# ADF4351_atmega8.net
KiCad netlist of a schematic drawn in EAGLE
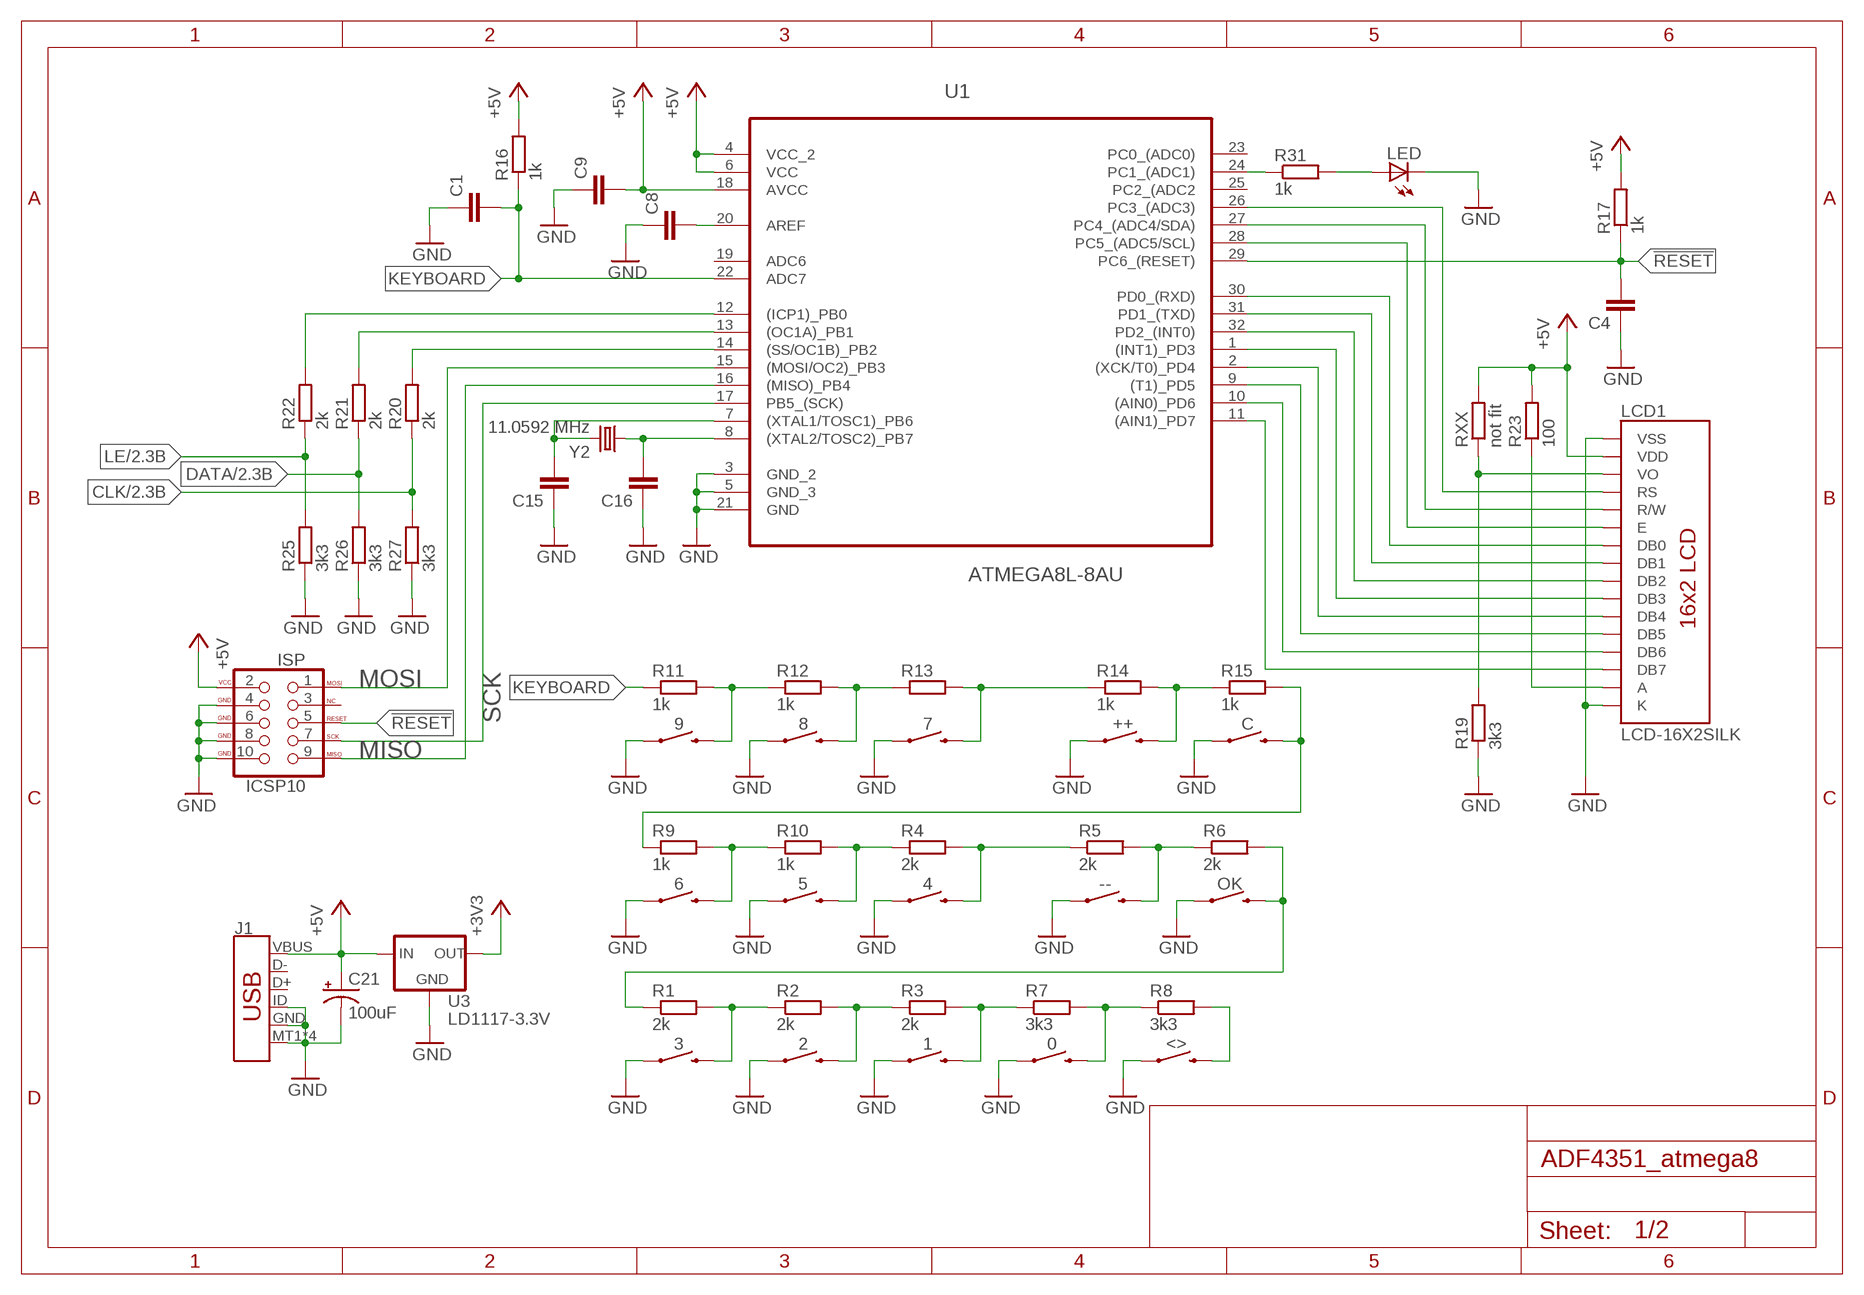
[diagram p0: schematic, sheet 1]
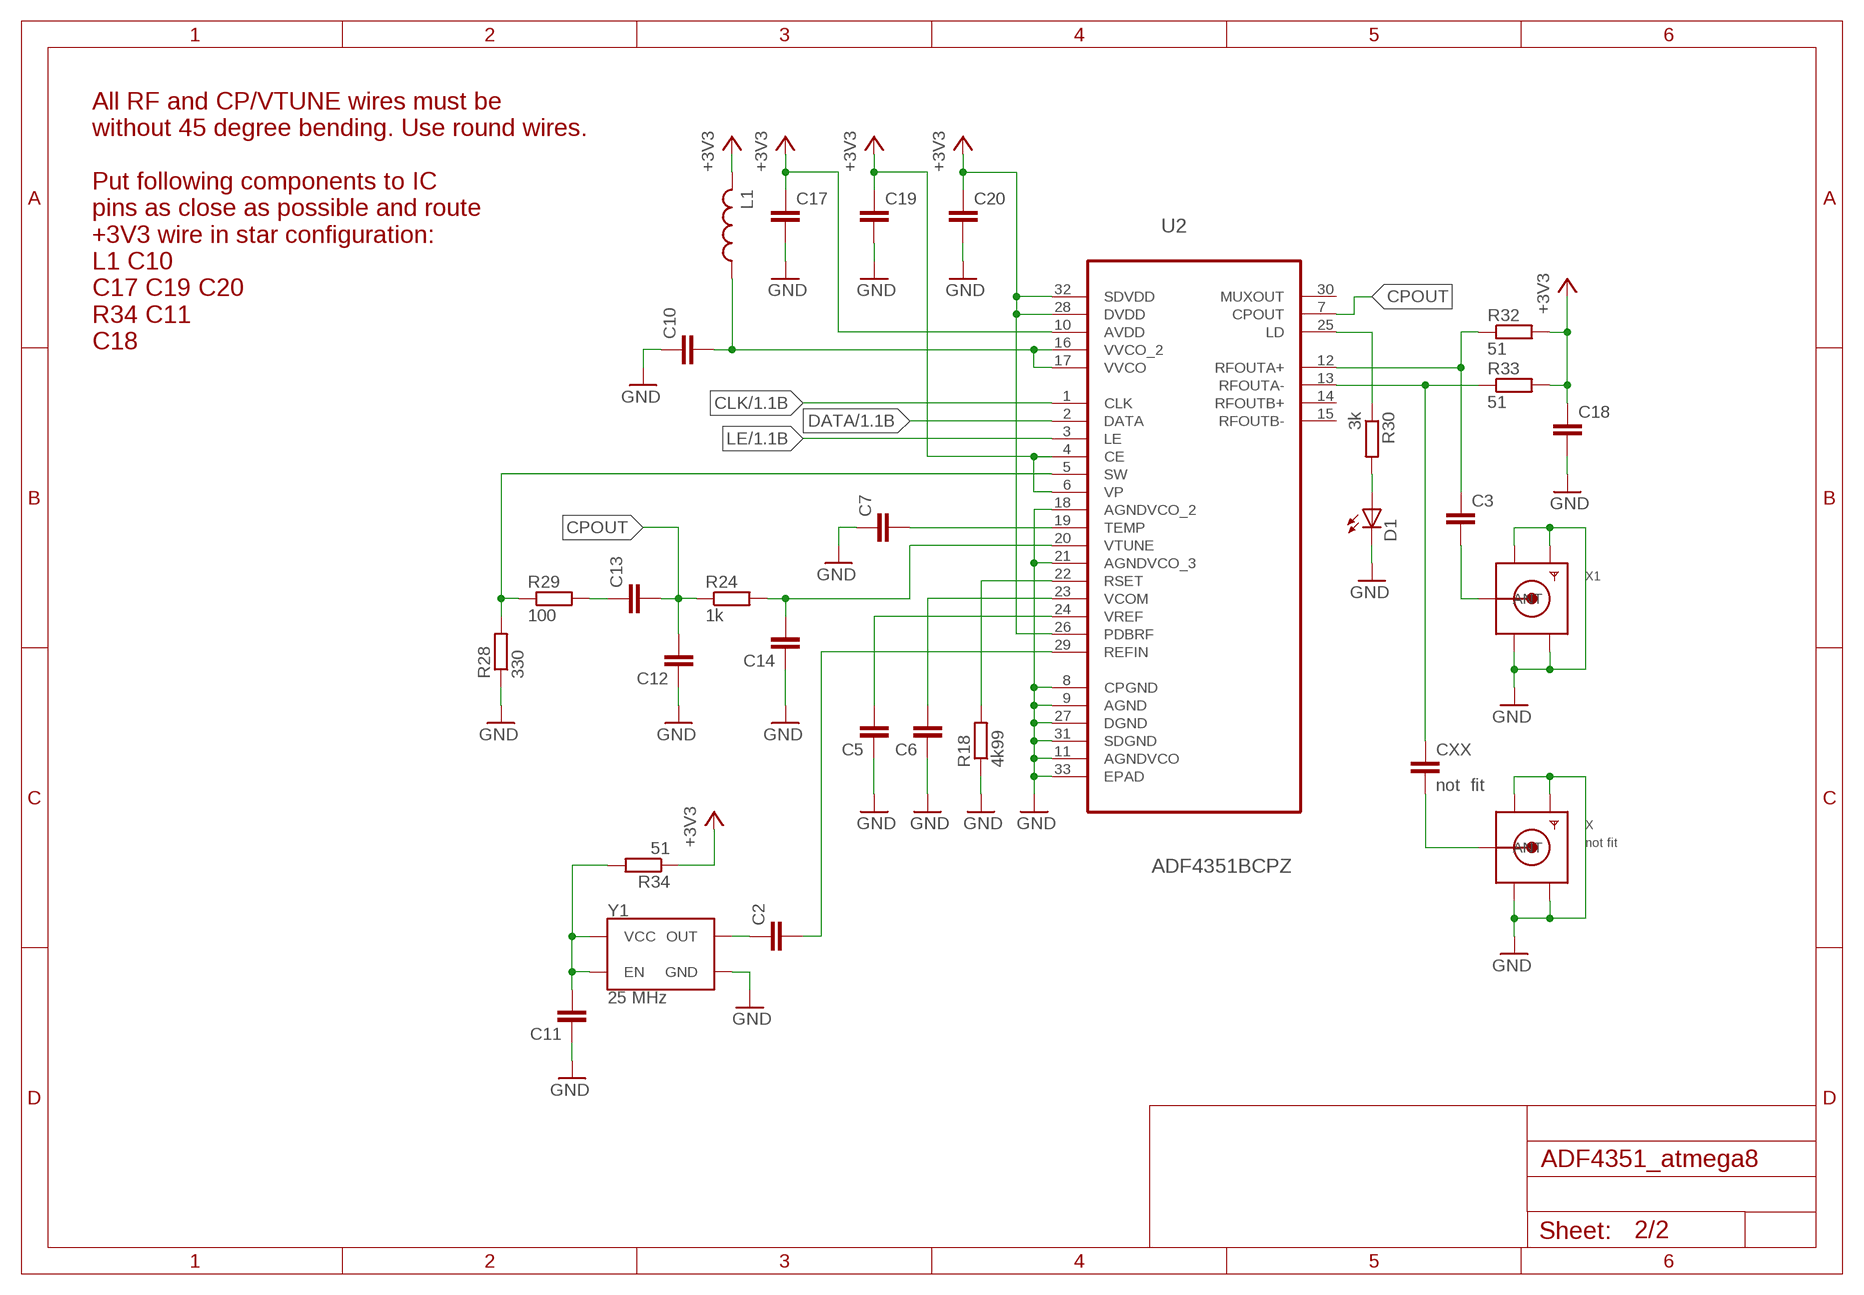
[diagram p1: schematic, sheet 2]

(export (version "E")
  (design (tool "Eeschema 10.0.6"))
  (components
    (comp (ref "C2")
      (value "C-EUC0805")
      (footprint "eagle-import:C0805")
      (libsource (lib "eagle-import") (part "C-EUC0805"))
    )
    (comp (ref "C3")
      (value "C-EUC0805")
      (footprint "eagle-import:C0805")
      (libsource (lib "eagle-import") (part "C-EUC0805"))
    )
    (comp (ref "C5")
      (value "C-EUC0805")
      (footprint "eagle-import:C0805")
      (libsource (lib "eagle-import") (part "C-EUC0805"))
    )
    (comp (ref "C6")
      (value "C-EUC0805")
      (footprint "eagle-import:C0805")
      (libsource (lib "eagle-import") (part "C-EUC0805"))
    )
    (comp (ref "C7")
      (value "C-EUC0805")
      (footprint "eagle-import:C0805")
      (libsource (lib "eagle-import") (part "C-EUC0805"))
    )
    (comp (ref "C10")
      (value "C-EUC0805")
      (footprint "eagle-import:C0805")
      (libsource (lib "eagle-import") (part "C-EUC0805"))
    )
    (comp (ref "C11")
      (value "C-EUC0805")
      (footprint "eagle-import:C0805")
      (libsource (lib "eagle-import") (part "C-EUC0805"))
    )
    (comp (ref "C12")
      (value "C-EUC0805")
      (footprint "eagle-import:C0805")
      (libsource (lib "eagle-import") (part "C-EUC0805"))
    )
    (comp (ref "C13")
      (value "C-EUC0805")
      (footprint "eagle-import:C0805")
      (libsource (lib "eagle-import") (part "C-EUC0805"))
    )
    (comp (ref "C14")
      (value "C-EUC0805")
      (footprint "eagle-import:C0805")
      (libsource (lib "eagle-import") (part "C-EUC0805"))
    )
    (comp (ref "C17")
      (value "C-EUC0805")
      (footprint "eagle-import:C0805")
      (libsource (lib "eagle-import") (part "C-EUC0805"))
    )
    (comp (ref "C18")
      (value "C-EUC0805")
      (footprint "eagle-import:C0805")
      (libsource (lib "eagle-import") (part "C-EUC0805"))
    )
    (comp (ref "C19")
      (value "C-EUC0805")
      (footprint "eagle-import:C0805")
      (libsource (lib "eagle-import") (part "C-EUC0805"))
    )
    (comp (ref "C20")
      (value "C-EUC0805")
      (footprint "eagle-import:C0805")
      (libsource (lib "eagle-import") (part "C-EUC0805"))
    )
    (comp (ref "CXX")
      (value "not fit")
      (footprint "eagle-import:C0805")
      (libsource (lib "eagle-import") (part "C-EUC0805"))
    )
    (comp (ref "D1")
      (value "LEDSML0805")
      (footprint "eagle-import:SML0805")
      (libsource (lib "eagle-import") (part "LEDSML0805"))
    )
    (comp (ref "L1")
      (value "L-USL2012C")
      (footprint "eagle-import:L2012C")
      (libsource (lib "eagle-import") (part "L-USL2012C"))
    )
    (comp (ref "R18")
      (value "4k99")
      (footprint "eagle-import:R0805")
      (libsource (lib "eagle-import") (part "R-EU_R0805"))
    )
    (comp (ref "R24")
      (value "1k")
      (footprint "eagle-import:R0805")
      (libsource (lib "eagle-import") (part "R-EU_R0805"))
    )
    (comp (ref "R28")
      (value "330")
      (footprint "eagle-import:R0805")
      (libsource (lib "eagle-import") (part "R-EU_R0805"))
    )
    (comp (ref "R29")
      (value "100")
      (footprint "eagle-import:R0805")
      (libsource (lib "eagle-import") (part "R-EU_R0805"))
    )
    (comp (ref "R30")
      (value "3k")
      (footprint "eagle-import:R0805")
      (libsource (lib "eagle-import") (part "R-EU_R0805"))
    )
    (comp (ref "R32")
      (value "51")
      (footprint "eagle-import:R0805")
      (libsource (lib "eagle-import") (part "R-EU_R0805"))
    )
    (comp (ref "R33")
      (value "51")
      (footprint "eagle-import:R0805")
      (libsource (lib "eagle-import") (part "R-EU_R0805"))
    )
    (comp (ref "R34")
      (value "51")
      (footprint "eagle-import:R0805")
      (libsource (lib "eagle-import") (part "R-EU_R0805"))
    )
    (comp (ref "U2")
      (value "ADF4351BCPZ")
      (footprint "eagle-import:QFN50P500X500X100-33N")
      (libsource (lib "eagle-import") (part "ADF4351BCPZ"))
    )
    (comp (ref "X")
      (value "not fit")
      (footprint "eagle-import:SMA_EDGELAUNCH")
      (libsource (lib "eagle-import") (part "SMACONNECTOR_EDGE"))
    )
    (comp (ref "X1")
      (value "SMACONNECTOR_EDGE")
      (footprint "eagle-import:SMA_EDGELAUNCH")
      (libsource (lib "eagle-import") (part "SMACONNECTOR_EDGE"))
    )
    (comp (ref "Y1")
      (value "25 MHz")
      (footprint "eagle-import:OSCILLATOR-SMD-7X5-4PAD")
      (libsource (lib "eagle-import") (part "OSCILLATORSMD-7X5-4PAD"))
    )
    (comp (ref "++")
      (value "MOMENTARY-SWITCH-SPST-SMD-6.2MM-TALL")
      (footprint "eagle-import:TACTILE_SWITCH_SMD_6.2MM_TALL")
      (libsource (lib "eagle-import") (part "MOMENTARY-SWITCH-SPST-SMD-6.2MM-TALL"))
    )
    (comp (ref "--")
      (value "MOMENTARY-SWITCH-SPST-SMD-6.2MM-TALL")
      (footprint "eagle-import:TACTILE_SWITCH_SMD_6.2MM_TALL")
      (libsource (lib "eagle-import") (part "MOMENTARY-SWITCH-SPST-SMD-6.2MM-TALL"))
    )
    (comp (ref "0")
      (value "MOMENTARY-SWITCH-SPST-SMD-6.2MM-TALL")
      (footprint "eagle-import:TACTILE_SWITCH_SMD_6.2MM_TALL")
      (libsource (lib "eagle-import") (part "MOMENTARY-SWITCH-SPST-SMD-6.2MM-TALL"))
    )
    (comp (ref "1")
      (value "MOMENTARY-SWITCH-SPST-SMD-6.2MM-TALL")
      (footprint "eagle-import:TACTILE_SWITCH_SMD_6.2MM_TALL")
      (libsource (lib "eagle-import") (part "MOMENTARY-SWITCH-SPST-SMD-6.2MM-TALL"))
    )
    (comp (ref "2")
      (value "MOMENTARY-SWITCH-SPST-SMD-6.2MM-TALL")
      (footprint "eagle-import:TACTILE_SWITCH_SMD_6.2MM_TALL")
      (libsource (lib "eagle-import") (part "MOMENTARY-SWITCH-SPST-SMD-6.2MM-TALL"))
    )
    (comp (ref "3")
      (value "MOMENTARY-SWITCH-SPST-SMD-6.2MM-TALL")
      (footprint "eagle-import:TACTILE_SWITCH_SMD_6.2MM_TALL")
      (libsource (lib "eagle-import") (part "MOMENTARY-SWITCH-SPST-SMD-6.2MM-TALL"))
    )
    (comp (ref "4")
      (value "MOMENTARY-SWITCH-SPST-SMD-6.2MM-TALL")
      (footprint "eagle-import:TACTILE_SWITCH_SMD_6.2MM_TALL")
      (libsource (lib "eagle-import") (part "MOMENTARY-SWITCH-SPST-SMD-6.2MM-TALL"))
    )
    (comp (ref "5")
      (value "MOMENTARY-SWITCH-SPST-SMD-6.2MM-TALL")
      (footprint "eagle-import:TACTILE_SWITCH_SMD_6.2MM_TALL")
      (libsource (lib "eagle-import") (part "MOMENTARY-SWITCH-SPST-SMD-6.2MM-TALL"))
    )
    (comp (ref "6")
      (value "MOMENTARY-SWITCH-SPST-SMD-6.2MM-TALL")
      (footprint "eagle-import:TACTILE_SWITCH_SMD_6.2MM_TALL")
      (libsource (lib "eagle-import") (part "MOMENTARY-SWITCH-SPST-SMD-6.2MM-TALL"))
    )
    (comp (ref "7")
      (value "MOMENTARY-SWITCH-SPST-SMD-6.2MM-TALL")
      (footprint "eagle-import:TACTILE_SWITCH_SMD_6.2MM_TALL")
      (libsource (lib "eagle-import") (part "MOMENTARY-SWITCH-SPST-SMD-6.2MM-TALL"))
    )
    (comp (ref "8")
      (value "MOMENTARY-SWITCH-SPST-SMD-6.2MM-TALL")
      (footprint "eagle-import:TACTILE_SWITCH_SMD_6.2MM_TALL")
      (libsource (lib "eagle-import") (part "MOMENTARY-SWITCH-SPST-SMD-6.2MM-TALL"))
    )
    (comp (ref "9")
      (value "MOMENTARY-SWITCH-SPST-SMD-6.2MM-TALL")
      (footprint "eagle-import:TACTILE_SWITCH_SMD_6.2MM_TALL")
      (libsource (lib "eagle-import") (part "MOMENTARY-SWITCH-SPST-SMD-6.2MM-TALL"))
    )
    (comp (ref "<>")
      (value "MOMENTARY-SWITCH-SPST-SMD-6.2MM-TALL")
      (footprint "eagle-import:TACTILE_SWITCH_SMD_6.2MM_TALL")
      (libsource (lib "eagle-import") (part "MOMENTARY-SWITCH-SPST-SMD-6.2MM-TALL"))
    )
    (comp (ref "C")
      (value "MOMENTARY-SWITCH-SPST-SMD-6.2MM-TALL")
      (footprint "eagle-import:TACTILE_SWITCH_SMD_6.2MM_TALL")
      (libsource (lib "eagle-import") (part "MOMENTARY-SWITCH-SPST-SMD-6.2MM-TALL"))
    )
    (comp (ref "C1")
      (value "C-EUC0805")
      (footprint "eagle-import:C0805")
      (libsource (lib "eagle-import") (part "C-EUC0805"))
    )
    (comp (ref "C4")
      (value "C-EUC0805")
      (footprint "eagle-import:C0805")
      (libsource (lib "eagle-import") (part "C-EUC0805"))
    )
    (comp (ref "C8")
      (value "C-EUC0805")
      (footprint "eagle-import:C0805")
      (libsource (lib "eagle-import") (part "C-EUC0805"))
    )
    (comp (ref "C9")
      (value "C-EUC0805")
      (footprint "eagle-import:C0805")
      (libsource (lib "eagle-import") (part "C-EUC0805"))
    )
    (comp (ref "C15")
      (value "C-EUC0805")
      (footprint "eagle-import:C0805")
      (libsource (lib "eagle-import") (part "C-EUC0805"))
    )
    (comp (ref "C16")
      (value "C-EUC0805")
      (footprint "eagle-import:C0805")
      (libsource (lib "eagle-import") (part "C-EUC0805"))
    )
    (comp (ref "C21")
      (value "100uF")
      (footprint "eagle-import:E5-5")
      (libsource (lib "eagle-import") (part "CPOL-USE5-5"))
    )
    (comp (ref "ISP")
      (value "ICSP10")
      (footprint "eagle-import:2X5")
      (libsource (lib "eagle-import") (part "AVR_SPI_PROG_5X2PTH"))
    )
    (comp (ref "J1")
      (value "USB_MICRO-B_SMT")
      (footprint "eagle-import:USB-MICROB")
      (libsource (lib "eagle-import") (part "USB_MICRO-B_SMT"))
    )
    (comp (ref "LCD1")
      (value "LCD-16X2SILK")
      (footprint "eagle-import:LCD-16X2")
      (libsource (lib "eagle-import") (part "LCD-16X2SILK"))
    )
    (comp (ref "LED")
      (value "LEDSML0805")
      (footprint "eagle-import:SML0805")
      (libsource (lib "eagle-import") (part "LEDSML0805"))
    )
    (comp (ref "OK")
      (value "MOMENTARY-SWITCH-SPST-SMD-6.2MM-TALL")
      (footprint "eagle-import:TACTILE_SWITCH_SMD_6.2MM_TALL")
      (libsource (lib "eagle-import") (part "MOMENTARY-SWITCH-SPST-SMD-6.2MM-TALL"))
    )
    (comp (ref "R1")
      (value "2k")
      (footprint "eagle-import:R0805")
      (libsource (lib "eagle-import") (part "R-EU_R0805"))
    )
    (comp (ref "R2")
      (value "2k")
      (footprint "eagle-import:R0805")
      (libsource (lib "eagle-import") (part "R-EU_R0805"))
    )
    (comp (ref "R3")
      (value "2k")
      (footprint "eagle-import:R0805")
      (libsource (lib "eagle-import") (part "R-EU_R0805"))
    )
    (comp (ref "R4")
      (value "2k")
      (footprint "eagle-import:R0805")
      (libsource (lib "eagle-import") (part "R-EU_R0805"))
    )
    (comp (ref "R5")
      (value "2k")
      (footprint "eagle-import:R0805")
      (libsource (lib "eagle-import") (part "R-EU_R0805"))
    )
    (comp (ref "R6")
      (value "2k")
      (footprint "eagle-import:R0805")
      (libsource (lib "eagle-import") (part "R-EU_R0805"))
    )
    (comp (ref "R7")
      (value "3k3")
      (footprint "eagle-import:R0805")
      (libsource (lib "eagle-import") (part "R-EU_R0805"))
    )
    (comp (ref "R8")
      (value "3k3")
      (footprint "eagle-import:R0805")
      (libsource (lib "eagle-import") (part "R-EU_R0805"))
    )
    (comp (ref "R9")
      (value "1k")
      (footprint "eagle-import:R0805")
      (libsource (lib "eagle-import") (part "R-EU_R0805"))
    )
    (comp (ref "R10")
      (value "1k")
      (footprint "eagle-import:R0805")
      (libsource (lib "eagle-import") (part "R-EU_R0805"))
    )
    (comp (ref "R11")
      (value "1k")
      (footprint "eagle-import:R0805")
      (libsource (lib "eagle-import") (part "R-EU_R0805"))
    )
    (comp (ref "R12")
      (value "1k")
      (footprint "eagle-import:R0805")
      (libsource (lib "eagle-import") (part "R-EU_R0805"))
    )
    (comp (ref "R13")
      (value "R-EU_R0805")
      (footprint "eagle-import:R0805")
      (libsource (lib "eagle-import") (part "R-EU_R0805"))
    )
    (comp (ref "R14")
      (value "1k")
      (footprint "eagle-import:R0805")
      (libsource (lib "eagle-import") (part "R-EU_R0805"))
    )
    (comp (ref "R15")
      (value "1k")
      (footprint "eagle-import:R0805")
      (libsource (lib "eagle-import") (part "R-EU_R0805"))
    )
    (comp (ref "R16")
      (value "1k")
      (footprint "eagle-import:R0805")
      (libsource (lib "eagle-import") (part "R-EU_R0805"))
    )
    (comp (ref "R17")
      (value "1k")
      (footprint "eagle-import:R0805")
      (libsource (lib "eagle-import") (part "R-EU_R0805"))
    )
    (comp (ref "R19")
      (value "3k3")
      (footprint "eagle-import:R0805")
      (libsource (lib "eagle-import") (part "R-EU_R0805"))
    )
    (comp (ref "R20")
      (value "2k")
      (footprint "eagle-import:R0805")
      (libsource (lib "eagle-import") (part "R-EU_R0805"))
    )
    (comp (ref "R21")
      (value "2k")
      (footprint "eagle-import:R0805")
      (libsource (lib "eagle-import") (part "R-EU_R0805"))
    )
    (comp (ref "R22")
      (value "2k")
      (footprint "eagle-import:R0805")
      (libsource (lib "eagle-import") (part "R-EU_R0805"))
    )
    (comp (ref "R23")
      (value "100")
      (footprint "eagle-import:R0805")
      (libsource (lib "eagle-import") (part "R-EU_R0805"))
    )
    (comp (ref "R25")
      (value "3k3")
      (footprint "eagle-import:R0805")
      (libsource (lib "eagle-import") (part "R-EU_R0805"))
    )
    (comp (ref "R26")
      (value "3k3")
      (footprint "eagle-import:R0805")
      (libsource (lib "eagle-import") (part "R-EU_R0805"))
    )
    (comp (ref "R27")
      (value "3k3")
      (footprint "eagle-import:R0805")
      (libsource (lib "eagle-import") (part "R-EU_R0805"))
    )
    (comp (ref "R31")
      (value "1k")
      (footprint "eagle-import:R0805")
      (libsource (lib "eagle-import") (part "R-EU_R0805"))
    )
    (comp (ref "RXX")
      (value "not fit")
      (footprint "eagle-import:R0805")
      (libsource (lib "eagle-import") (part "R-EU_R0805"))
    )
    (comp (ref "U1")
      (value "ATMEGA8L-8AU")
      (footprint "eagle-import:QFP80P900X900X120-32N")
      (libsource (lib "eagle-import") (part "ATMEGA8L-8AU"))
    )
    (comp (ref "U3")
      (value "LD1117-3.3V")
      (footprint "eagle-import:SOT223")
      (libsource (lib "eagle-import") (part "V_REG_LD1117VXXLD1117-SMD"))
    )
    (comp (ref "Y2")
      (value "11.0592 MHz")
      (footprint "eagle-import:HC49_S")
      (libsource (lib "eagle-import") (part "CRYSTALHC49S"))
    )
  )
  (nets
    (net (code "1") (name "+3V3") (class "Default")
      (node (ref "C17") (pin "1") (pinfunction "1_1") (pintype "passive"))
      (node (ref "C18") (pin "1") (pinfunction "1_1") (pintype "passive"))
      (node (ref "C19") (pin "1") (pinfunction "1_1") (pintype "passive"))
      (node (ref "C20") (pin "1") (pinfunction "1_1") (pintype "passive"))
      (node (ref "L1") (pin "2") (pinfunction "2_2") (pintype "passive"))
      (node (ref "R32") (pin "2") (pinfunction "2_2") (pintype "passive"))
      (node (ref "R33") (pin "2") (pinfunction "2_2") (pintype "passive"))
      (node (ref "R34") (pin "1") (pinfunction "1_1") (pintype "passive"))
      (node (ref "U2") (pin "10") (pinfunction "AVDD_10") (pintype "power_in"))
      (node (ref "U2") (pin "26") (pinfunction "PDBRF_26") (pintype "passive"))
      (node (ref "U2") (pin "28") (pinfunction "DVDD_28") (pintype "power_in"))
      (node (ref "U2") (pin "32") (pinfunction "SDVDD_32") (pintype "passive"))
      (node (ref "U2") (pin "4") (pinfunction "CE_4") (pintype "input"))
      (node (ref "U2") (pin "6") (pinfunction "VP_6") (pintype "power_in"))
      (node (ref "U3") (pin "2") (pinfunction "OUT_2") (pintype "passive"))
    )
    (net (code "2") (name "+5V") (class "Default")
      (node (ref "C21") (pin "+") (pinfunction "+_+") (pintype "passive"))
      (node (ref "C9") (pin "2") (pinfunction "2_2") (pintype "passive"))
      (node (ref "ISP") (pin "2") (pinfunction "VCC_2") (pintype "power_in"))
      (node (ref "J1") (pin "VBUS") (pinfunction "VBUS_VBUS") (pintype "power_in"))
      (node (ref "LCD1") (pin "2") (pinfunction "VDD_2") (pintype "power_in"))
      (node (ref "R16") (pin "2") (pinfunction "2_2") (pintype "passive"))
      (node (ref "R17") (pin "2") (pinfunction "2_2") (pintype "passive"))
      (node (ref "R23") (pin "2") (pinfunction "2_2") (pintype "passive"))
      (node (ref "RXX") (pin "2") (pinfunction "2_2") (pintype "passive"))
      (node (ref "U1") (pin "18") (pinfunction "AVCC_18") (pintype "power_in"))
      (node (ref "U1") (pin "4") (pinfunction "VCC_2_4") (pintype "power_in"))
      (node (ref "U1") (pin "6") (pinfunction "VCC_6") (pintype "power_in"))
      (node (ref "U3") (pin "3") (pinfunction "IN_3") (pintype "input"))
    )
    (net (code "3") (name "CLK") (class "Default")
      (node (ref "R20") (pin "1") (pinfunction "1_1") (pintype "passive"))
      (node (ref "R27") (pin "2") (pinfunction "2_2") (pintype "passive"))
      (node (ref "U2") (pin "1") (pinfunction "CLK_1") (pintype "input"))
    )
    (net (code "4") (name "CPOUT") (class "Default")
      (node (ref "C12") (pin "2") (pinfunction "2_2") (pintype "passive"))
      (node (ref "C13") (pin "2") (pinfunction "2_2") (pintype "passive"))
      (node (ref "R24") (pin "1") (pinfunction "1_1") (pintype "passive"))
      (node (ref "U2") (pin "7") (pinfunction "CPOUT_7") (pintype "output"))
    )
    (net (code "5") (name "DATA") (class "Default")
      (node (ref "R21") (pin "1") (pinfunction "1_1") (pintype "passive"))
      (node (ref "R26") (pin "2") (pinfunction "2_2") (pintype "passive"))
      (node (ref "U2") (pin "2") (pinfunction "DATA_2") (pintype "input"))
    )
    (net (code "6") (name "GND") (class "Default")
      (node (ref "++") (pin "A2") (pinfunction "1_A2") (pintype "passive"))
      (node (ref "--") (pin "A2") (pinfunction "1_A2") (pintype "passive"))
      (node (ref "0") (pin "A2") (pinfunction "1_A2") (pintype "passive"))
      (node (ref "1") (pin "A2") (pinfunction "1_A2") (pintype "passive"))
      (node (ref "2") (pin "A2") (pinfunction "1_A2") (pintype "passive"))
      (node (ref "3") (pin "A2") (pinfunction "1_A2") (pintype "passive"))
      (node (ref "4") (pin "A2") (pinfunction "1_A2") (pintype "passive"))
      (node (ref "5") (pin "A2") (pinfunction "1_A2") (pintype "passive"))
      (node (ref "6") (pin "A2") (pinfunction "1_A2") (pintype "passive"))
      (node (ref "7") (pin "A2") (pinfunction "1_A2") (pintype "passive"))
      (node (ref "8") (pin "A2") (pinfunction "1_A2") (pintype "passive"))
      (node (ref "9") (pin "A2") (pinfunction "1_A2") (pintype "passive"))
      (node (ref "<>") (pin "A2") (pinfunction "1_A2") (pintype "passive"))
      (node (ref "C") (pin "A2") (pinfunction "1_A2") (pintype "passive"))
      (node (ref "C1") (pin "1") (pinfunction "1_1") (pintype "passive"))
      (node (ref "C10") (pin "1") (pinfunction "1_1") (pintype "passive"))
      (node (ref "C11") (pin "1") (pinfunction "1_1") (pintype "passive"))
      (node (ref "C12") (pin "1") (pinfunction "1_1") (pintype "passive"))
      (node (ref "C14") (pin "1") (pinfunction "1_1") (pintype "passive"))
      (node (ref "C15") (pin "1") (pinfunction "1_1") (pintype "passive"))
      (node (ref "C16") (pin "1") (pinfunction "1_1") (pintype "passive"))
      (node (ref "C17") (pin "2") (pinfunction "2_2") (pintype "passive"))
      (node (ref "C18") (pin "2") (pinfunction "2_2") (pintype "passive"))
      (node (ref "C19") (pin "2") (pinfunction "2_2") (pintype "passive"))
      (node (ref "C20") (pin "2") (pinfunction "2_2") (pintype "passive"))
      (node (ref "C21") (pin "-") (pinfunction "-_-") (pintype "passive"))
      (node (ref "C4") (pin "1") (pinfunction "1_1") (pintype "passive"))
      (node (ref "C5") (pin "1") (pinfunction "1_1") (pintype "passive"))
      (node (ref "C6") (pin "1") (pinfunction "1_1") (pintype "passive"))
      (node (ref "C7") (pin "1") (pinfunction "1_1") (pintype "passive"))
      (node (ref "C8") (pin "1") (pinfunction "1_1") (pintype "passive"))
      (node (ref "C9") (pin "1") (pinfunction "1_1") (pintype "passive"))
      (node (ref "D1") (pin "C") (pinfunction "C_C") (pintype "passive"))
      (node (ref "ISP") (pin "10") (pinfunction "GND_10") (pintype "power_in"))
      (node (ref "ISP") (pin "4") (pinfunction "GND_4") (pintype "power_in"))
      (node (ref "ISP") (pin "6") (pinfunction "GND_6") (pintype "power_in"))
      (node (ref "ISP") (pin "8") (pinfunction "GND_8") (pintype "power_in"))
      (node (ref "J1") (pin "GND") (pinfunction "GND_GND") (pintype "power_in"))
      (node (ref "J1") (pin "ID") (pinfunction "ID_ID") (pintype "bidirectional"))
      (node (ref "J1") (pin "MT1") (pinfunction "SHIELD_MT1") (pintype "bidirectional"))
      (node (ref "J1") (pin "MT2") (pinfunction "SHIELD_MT2") (pintype "bidirectional"))
      (node (ref "J1") (pin "P$1") (pinfunction "SHIELD_P$1") (pintype "bidirectional"))
      (node (ref "J1") (pin "P$2") (pinfunction "SHIELD_P$2") (pintype "bidirectional"))
      (node (ref "LCD1") (pin "1") (pinfunction "VSS_1") (pintype "power_in"))
      (node (ref "LCD1") (pin "16") (pinfunction "K_16") (pintype "power_in"))
      (node (ref "LED") (pin "C") (pinfunction "C_C") (pintype "passive"))
      (node (ref "OK") (pin "A2") (pinfunction "1_A2") (pintype "passive"))
      (node (ref "R18") (pin "1") (pinfunction "1_1") (pintype "passive"))
      (node (ref "R19") (pin "1") (pinfunction "1_1") (pintype "passive"))
      (node (ref "R25") (pin "1") (pinfunction "1_1") (pintype "passive"))
      (node (ref "R26") (pin "1") (pinfunction "1_1") (pintype "passive"))
      (node (ref "R27") (pin "1") (pinfunction "1_1") (pintype "passive"))
      (node (ref "R28") (pin "1") (pinfunction "1_1") (pintype "passive"))
      (node (ref "U1") (pin "21") (pinfunction "GND_21") (pintype "passive"))
      (node (ref "U1") (pin "3") (pinfunction "GND_2_3") (pintype "passive"))
      (node (ref "U1") (pin "5") (pinfunction "GND_3_5") (pintype "passive"))
      (node (ref "U2") (pin "11") (pinfunction "AGNDVCO_11") (pintype "passive"))
      (node (ref "U2") (pin "18") (pinfunction "AGNDVCO_2_18") (pintype "passive"))
      (node (ref "U2") (pin "21") (pinfunction "AGNDVCO_3_21") (pintype "passive"))
      (node (ref "U2") (pin "27") (pinfunction "DGND_27") (pintype "passive"))
      (node (ref "U2") (pin "31") (pinfunction "SDGND_31") (pintype "passive"))
      (node (ref "U2") (pin "33") (pinfunction "EPAD_33") (pintype "passive"))
      (node (ref "U2") (pin "8") (pinfunction "CPGND_8") (pintype "passive"))
      (node (ref "U2") (pin "9") (pinfunction "AGND_9") (pintype "power_in"))
      (node (ref "U3") (pin "1") (pinfunction "GND_1") (pintype "input"))
      (node (ref "X") (pin "GND@1") (pinfunction "GND4_GND@1") (pintype "power_in"))
      (node (ref "X") (pin "GND@2") (pinfunction "GND3_GND@2") (pintype "power_in"))
      (node (ref "X") (pin "GND@3") (pinfunction "GND2_GND@3") (pintype "power_in"))
      (node (ref "X") (pin "GND@4") (pinfunction "GND1_GND@4") (pintype "power_in"))
      (node (ref "X1") (pin "GND@1") (pinfunction "GND4_GND@1") (pintype "power_in"))
      (node (ref "X1") (pin "GND@2") (pinfunction "GND3_GND@2") (pintype "power_in"))
      (node (ref "X1") (pin "GND@3") (pinfunction "GND2_GND@3") (pintype "power_in"))
      (node (ref "X1") (pin "GND@4") (pinfunction "GND1_GND@4") (pintype "power_in"))
      (node (ref "Y1") (pin "2") (pinfunction "GND_2") (pintype "bidirectional"))
    )
    (net (code "7") (name "KEYBOARD") (class "Default")
      (node (ref "C1") (pin "2") (pinfunction "2_2") (pintype "passive"))
      (node (ref "R11") (pin "1") (pinfunction "1_1") (pintype "passive"))
      (node (ref "R16") (pin "1") (pinfunction "1_1") (pintype "passive"))
      (node (ref "U1") (pin "22") (pinfunction "ADC7_22") (pintype "input"))
    )
    (net (code "8") (name "LE") (class "Default")
      (node (ref "R22") (pin "1") (pinfunction "1_1") (pintype "passive"))
      (node (ref "R25") (pin "2") (pinfunction "2_2") (pintype "passive"))
      (node (ref "U2") (pin "3") (pinfunction "LE_3") (pintype "input"))
    )
    (net (code "9") (name "MISO") (class "Default")
      (node (ref "ISP") (pin "9") (pinfunction "MISO_9") (pintype "passive"))
      (node (ref "U1") (pin "16") (pinfunction "(MISO)_PB4_16") (pintype "bidirectional"))
    )
    (net (code "10") (name "MOSI") (class "Default")
      (node (ref "ISP") (pin "1") (pinfunction "MOSI_1") (pintype "passive"))
      (node (ref "U1") (pin "15") (pinfunction "(MOSI/OC2)_PB3_15") (pintype "bidirectional"))
    )
    (net (code "11") (name "Net-(++-2)") (class "Default")
      (node (ref "++") (pin "B2") (pinfunction "2_B2") (pintype "passive"))
      (node (ref "R14") (pin "2") (pinfunction "2_2") (pintype "passive"))
      (node (ref "R15") (pin "1") (pinfunction "1_1") (pintype "passive"))
    )
    (net (code "12") (name "Net-(---2)") (class "Default")
      (node (ref "--") (pin "B2") (pinfunction "2_B2") (pintype "passive"))
      (node (ref "R5") (pin "2") (pinfunction "2_2") (pintype "passive"))
      (node (ref "R6") (pin "1") (pinfunction "1_1") (pintype "passive"))
    )
    (net (code "13") (name "Net-(0-2)") (class "Default")
      (node (ref "0") (pin "B2") (pinfunction "2_B2") (pintype "passive"))
      (node (ref "R7") (pin "2") (pinfunction "2_2") (pintype "passive"))
      (node (ref "R8") (pin "1") (pinfunction "1_1") (pintype "passive"))
    )
    (net (code "14") (name "Net-(1-2)") (class "Default")
      (node (ref "1") (pin "B2") (pinfunction "2_B2") (pintype "passive"))
      (node (ref "R3") (pin "2") (pinfunction "2_2") (pintype "passive"))
      (node (ref "R7") (pin "1") (pinfunction "1_1") (pintype "passive"))
    )
    (net (code "15") (name "Net-(2-2)") (class "Default")
      (node (ref "2") (pin "B2") (pinfunction "2_B2") (pintype "passive"))
      (node (ref "R2") (pin "2") (pinfunction "2_2") (pintype "passive"))
      (node (ref "R3") (pin "1") (pinfunction "1_1") (pintype "passive"))
    )
    (net (code "16") (name "Net-(3-2)") (class "Default")
      (node (ref "3") (pin "B2") (pinfunction "2_B2") (pintype "passive"))
      (node (ref "R1") (pin "2") (pinfunction "2_2") (pintype "passive"))
      (node (ref "R2") (pin "1") (pinfunction "1_1") (pintype "passive"))
    )
    (net (code "17") (name "Net-(4-2)") (class "Default")
      (node (ref "4") (pin "B2") (pinfunction "2_B2") (pintype "passive"))
      (node (ref "R4") (pin "2") (pinfunction "2_2") (pintype "passive"))
      (node (ref "R5") (pin "1") (pinfunction "1_1") (pintype "passive"))
    )
    (net (code "18") (name "Net-(5-2)") (class "Default")
      (node (ref "5") (pin "B2") (pinfunction "2_B2") (pintype "passive"))
      (node (ref "R10") (pin "2") (pinfunction "2_2") (pintype "passive"))
      (node (ref "R4") (pin "1") (pinfunction "1_1") (pintype "passive"))
    )
    (net (code "19") (name "Net-(6-2)") (class "Default")
      (node (ref "6") (pin "B2") (pinfunction "2_B2") (pintype "passive"))
      (node (ref "R10") (pin "1") (pinfunction "1_1") (pintype "passive"))
      (node (ref "R9") (pin "2") (pinfunction "2_2") (pintype "passive"))
    )
    (net (code "20") (name "Net-(7-2)") (class "Default")
      (node (ref "7") (pin "B2") (pinfunction "2_B2") (pintype "passive"))
      (node (ref "R13") (pin "2") (pinfunction "2_2") (pintype "passive"))
      (node (ref "R14") (pin "1") (pinfunction "1_1") (pintype "passive"))
    )
    (net (code "21") (name "Net-(8-2)") (class "Default")
      (node (ref "8") (pin "B2") (pinfunction "2_B2") (pintype "passive"))
      (node (ref "R12") (pin "2") (pinfunction "2_2") (pintype "passive"))
      (node (ref "R13") (pin "1") (pinfunction "1_1") (pintype "passive"))
    )
    (net (code "22") (name "Net-(9-2)") (class "Default")
      (node (ref "9") (pin "B2") (pinfunction "2_B2") (pintype "passive"))
      (node (ref "R11") (pin "2") (pinfunction "2_2") (pintype "passive"))
      (node (ref "R12") (pin "1") (pinfunction "1_1") (pintype "passive"))
    )
    (net (code "23") (name "Net-(<>-2)") (class "Default")
      (node (ref "<>") (pin "B2") (pinfunction "2_B2") (pintype "passive"))
      (node (ref "R8") (pin "2") (pinfunction "2_2") (pintype "passive"))
    )
    (net (code "24") (name "Net-(C-2)") (class "Default")
      (node (ref "C") (pin "B2") (pinfunction "2_B2") (pintype "passive"))
      (node (ref "R15") (pin "2") (pinfunction "2_2") (pintype "passive"))
      (node (ref "R9") (pin "1") (pinfunction "1_1") (pintype "passive"))
    )
    (net (code "25") (name "Net-(C13-Pad1)") (class "Default")
      (node (ref "C13") (pin "1") (pinfunction "1_1") (pintype "passive"))
      (node (ref "R29") (pin "2") (pinfunction "2_2") (pintype "passive"))
    )
    (net (code "26") (name "Net-(D1-PadA)") (class "Default")
      (node (ref "D1") (pin "A") (pinfunction "A_A") (pintype "passive"))
      (node (ref "R30") (pin "2") (pinfunction "2_2") (pintype "passive"))
    )
    (net (code "27") (name "Net-(LCD1-A)") (class "Default")
      (node (ref "LCD1") (pin "15") (pinfunction "A_15") (pintype "power_in"))
      (node (ref "R23") (pin "1") (pinfunction "1_1") (pintype "passive"))
    )
    (net (code "28") (name "Net-(LCD1-DB0)") (class "Default")
      (node (ref "LCD1") (pin "7") (pinfunction "DB0_7") (pintype "bidirectional"))
      (node (ref "U1") (pin "30") (pinfunction "PD0_(RXD)_30") (pintype "bidirectional"))
    )
    (net (code "29") (name "Net-(LCD1-DB1)") (class "Default")
      (node (ref "LCD1") (pin "8") (pinfunction "DB1_8") (pintype "bidirectional"))
      (node (ref "U1") (pin "31") (pinfunction "PD1_(TXD)_31") (pintype "bidirectional"))
    )
    (net (code "30") (name "Net-(LCD1-DB2)") (class "Default")
      (node (ref "LCD1") (pin "9") (pinfunction "DB2_9") (pintype "bidirectional"))
      (node (ref "U1") (pin "32") (pinfunction "PD2_(INT0)_32") (pintype "bidirectional"))
    )
    (net (code "31") (name "Net-(LCD1-DB3)") (class "Default")
      (node (ref "LCD1") (pin "10") (pinfunction "DB3_10") (pintype "bidirectional"))
      (node (ref "U1") (pin "1") (pinfunction "(INT1)_PD3_1") (pintype "bidirectional"))
    )
    (net (code "32") (name "Net-(LCD1-DB4)") (class "Default")
      (node (ref "LCD1") (pin "11") (pinfunction "DB4_11") (pintype "bidirectional"))
      (node (ref "U1") (pin "2") (pinfunction "(XCK/T0)_PD4_2") (pintype "bidirectional"))
    )
    (net (code "33") (name "Net-(LCD1-DB5)") (class "Default")
      (node (ref "LCD1") (pin "12") (pinfunction "DB5_12") (pintype "bidirectional"))
      (node (ref "U1") (pin "9") (pinfunction "(T1)_PD5_9") (pintype "bidirectional"))
    )
    (net (code "34") (name "Net-(LCD1-DB6)") (class "Default")
      (node (ref "LCD1") (pin "13") (pinfunction "DB6_13") (pintype "bidirectional"))
      (node (ref "U1") (pin "10") (pinfunction "(AIN0)_PD6_10") (pintype "bidirectional"))
    )
    (net (code "35") (name "Net-(LCD1-DB7)") (class "Default")
      (node (ref "LCD1") (pin "14") (pinfunction "DB7_14") (pintype "bidirectional"))
      (node (ref "U1") (pin "11") (pinfunction "(AIN1)_PD7_11") (pintype "bidirectional"))
    )
    (net (code "36") (name "Net-(LCD1-E)") (class "Default")
      (node (ref "LCD1") (pin "6") (pinfunction "E_6") (pintype "input"))
      (node (ref "U1") (pin "28") (pinfunction "PC5_(ADC5/SCL)_28") (pintype "bidirectional"))
    )
    (net (code "37") (name "Net-(LCD1-RS)") (class "Default")
      (node (ref "LCD1") (pin "4") (pinfunction "RS_4") (pintype "input"))
      (node (ref "U1") (pin "26") (pinfunction "PC3_(ADC3)_26") (pintype "bidirectional"))
    )
    (net (code "38") (name "Net-(LCD1-R{slash}W)") (class "Default")
      (node (ref "LCD1") (pin "5") (pinfunction "R/W_5") (pintype "input"))
      (node (ref "U1") (pin "27") (pinfunction "PC4_(ADC4/SDA)_27") (pintype "bidirectional"))
    )
    (net (code "39") (name "Net-(LCD1-VO)") (class "Default")
      (node (ref "LCD1") (pin "3") (pinfunction "VO_3") (pintype "bidirectional"))
      (node (ref "R19") (pin "2") (pinfunction "2_2") (pintype "passive"))
      (node (ref "RXX") (pin "1") (pinfunction "1_1") (pintype "passive"))
    )
    (net (code "40") (name "Net-(LED-PadA)") (class "Default")
      (node (ref "LED") (pin "A") (pinfunction "A_A") (pintype "passive"))
      (node (ref "R31") (pin "2") (pinfunction "2_2") (pintype "passive"))
    )
    (net (code "41") (name "Net-(OK-2)") (class "Default")
      (node (ref "OK") (pin "B2") (pinfunction "2_B2") (pintype "passive"))
      (node (ref "R1") (pin "1") (pinfunction "1_1") (pintype "passive"))
      (node (ref "R6") (pin "2") (pinfunction "2_2") (pintype "passive"))
    )
    (net (code "42") (name "Net-(U1-(ICP1)_PB0)") (class "Default")
      (node (ref "R22") (pin "2") (pinfunction "2_2") (pintype "passive"))
      (node (ref "U1") (pin "12") (pinfunction "(ICP1)_PB0_12") (pintype "bidirectional"))
    )
    (net (code "43") (name "Net-(U1-(OC1A)_PB1)") (class "Default")
      (node (ref "R21") (pin "2") (pinfunction "2_2") (pintype "passive"))
      (node (ref "U1") (pin "13") (pinfunction "(OC1A)_PB1_13") (pintype "bidirectional"))
    )
    (net (code "44") (name "Net-(U1-(SS{slash}OC1B)_PB2)") (class "Default")
      (node (ref "R20") (pin "2") (pinfunction "2_2") (pintype "passive"))
      (node (ref "U1") (pin "14") (pinfunction "(SS/OC1B)_PB2_14") (pintype "bidirectional"))
    )
    (net (code "45") (name "Net-(U1-(XTAL1{slash}TOSC1)_PB6)") (class "Default")
      (node (ref "C15") (pin "2") (pinfunction "2_2") (pintype "passive"))
      (node (ref "U1") (pin "7") (pinfunction "(XTAL1/TOSC1)_PB6_7") (pintype "input"))
      (node (ref "Y2") (pin "2") (pinfunction "2_2") (pintype "passive"))
    )
    (net (code "46") (name "Net-(U1-(XTAL2{slash}TOSC2)_PB7)") (class "Default")
      (node (ref "C16") (pin "2") (pinfunction "2_2") (pintype "passive"))
      (node (ref "U1") (pin "8") (pinfunction "(XTAL2/TOSC2)_PB7_8") (pintype "output"))
      (node (ref "Y2") (pin "1") (pinfunction "1_1") (pintype "passive"))
    )
    (net (code "47") (name "Net-(U1-AREF)") (class "Default")
      (node (ref "C8") (pin "2") (pinfunction "2_2") (pintype "passive"))
      (node (ref "U1") (pin "20") (pinfunction "AREF_20") (pintype "input"))
    )
    (net (code "48") (name "Net-(U1-PC1_(ADC1))") (class "Default")
      (node (ref "R31") (pin "1") (pinfunction "1_1") (pintype "passive"))
      (node (ref "U1") (pin "24") (pinfunction "PC1_(ADC1)_24") (pintype "bidirectional"))
    )
    (net (code "49") (name "Net-(U2-LD)") (class "Default")
      (node (ref "R30") (pin "1") (pinfunction "1_1") (pintype "passive"))
      (node (ref "U2") (pin "25") (pinfunction "LD_25") (pintype "output"))
    )
    (net (code "50") (name "Net-(U2-REFIN)") (class "Default")
      (node (ref "C2") (pin "2") (pinfunction "2_2") (pintype "passive"))
      (node (ref "U2") (pin "29") (pinfunction "REFIN_29") (pintype "input"))
    )
    (net (code "51") (name "Net-(U2-RFOUTA+)") (class "Default")
      (node (ref "C3") (pin "1") (pinfunction "1_1") (pintype "passive"))
      (node (ref "R32") (pin "1") (pinfunction "1_1") (pintype "passive"))
      (node (ref "U2") (pin "12") (pinfunction "RFOUTA+_12") (pintype "output"))
    )
    (net (code "52") (name "Net-(U2-RFOUTA-)") (class "Default")
      (node (ref "CXX") (pin "1") (pinfunction "1_1") (pintype "passive"))
      (node (ref "R33") (pin "1") (pinfunction "1_1") (pintype "passive"))
      (node (ref "U2") (pin "13") (pinfunction "RFOUTA-_13") (pintype "output"))
    )
    (net (code "53") (name "Net-(U2-RSET)") (class "Default")
      (node (ref "R18") (pin "2") (pinfunction "2_2") (pintype "passive"))
      (node (ref "U2") (pin "22") (pinfunction "RSET_22") (pintype "passive"))
    )
    (net (code "54") (name "Net-(U2-SW)") (class "Default")
      (node (ref "R28") (pin "2") (pinfunction "2_2") (pintype "passive"))
      (node (ref "R29") (pin "1") (pinfunction "1_1") (pintype "passive"))
      (node (ref "U2") (pin "5") (pinfunction "SW_5") (pintype "passive"))
    )
    (net (code "55") (name "Net-(U2-TEMP)") (class "Default")
      (node (ref "C7") (pin "2") (pinfunction "2_2") (pintype "passive"))
      (node (ref "U2") (pin "19") (pinfunction "TEMP_19") (pintype "passive"))
    )
    (net (code "56") (name "Net-(U2-VCOM)") (class "Default")
      (node (ref "C6") (pin "2") (pinfunction "2_2") (pintype "passive"))
      (node (ref "U2") (pin "23") (pinfunction "VCOM_23") (pintype "passive"))
    )
    (net (code "57") (name "Net-(U2-VREF)") (class "Default")
      (node (ref "C5") (pin "2") (pinfunction "2_2") (pintype "passive"))
      (node (ref "U2") (pin "24") (pinfunction "VREF_24") (pintype "input"))
    )
    (net (code "58") (name "Net-(U2-VTUNE)") (class "Default")
      (node (ref "C14") (pin "2") (pinfunction "2_2") (pintype "passive"))
      (node (ref "R24") (pin "2") (pinfunction "2_2") (pintype "passive"))
      (node (ref "U2") (pin "20") (pinfunction "VTUNE_20") (pintype "input"))
    )
    (net (code "59") (name "Net-(U2-VVCO)") (class "Default")
      (node (ref "C10") (pin "2") (pinfunction "2_2") (pintype "passive"))
      (node (ref "L1") (pin "1") (pinfunction "1_1") (pintype "passive"))
      (node (ref "U2") (pin "16") (pinfunction "VVCO_2_16") (pintype "power_in"))
      (node (ref "U2") (pin "17") (pinfunction "VVCO_17") (pintype "power_in"))
    )
    (net (code "60") (name "Net-(X-ANT)") (class "Default")
      (node (ref "CXX") (pin "2") (pinfunction "2_2") (pintype "passive"))
      (node (ref "X") (pin "P") (pinfunction "ANT_P") (pintype "bidirectional"))
    )
    (net (code "61") (name "Net-(X1-ANT)") (class "Default")
      (node (ref "C3") (pin "2") (pinfunction "2_2") (pintype "passive"))
      (node (ref "X1") (pin "P") (pinfunction "ANT_P") (pintype "bidirectional"))
    )
    (net (code "62") (name "Net-(Y1-EN)") (class "Default")
      (node (ref "C11") (pin "2") (pinfunction "2_2") (pintype "passive"))
      (node (ref "R34") (pin "2") (pinfunction "2_2") (pintype "passive"))
      (node (ref "Y1") (pin "1") (pinfunction "EN_1") (pintype "bidirectional"))
      (node (ref "Y1") (pin "4") (pinfunction "VCC_4") (pintype "bidirectional"))
    )
    (net (code "63") (name "Net-(Y1-OUT)") (class "Default")
      (node (ref "C2") (pin "1") (pinfunction "1_1") (pintype "passive"))
      (node (ref "Y1") (pin "3") (pinfunction "OUT_3") (pintype "bidirectional"))
    )
    (net (code "64") (name "SCK") (class "Default")
      (node (ref "ISP") (pin "7") (pinfunction "SCK_7") (pintype "passive"))
      (node (ref "U1") (pin "17") (pinfunction "PB5_(SCK)_17") (pintype "bidirectional"))
    )
    (net (code "65") (name "unconnected-(ISP-NC-Pad3)") (class "Default")
      (node (ref "ISP") (pin "3") (pinfunction "NC_3") (pintype "no_connect"))
    )
    (net (code "66") (name "unconnected-(J1-PadD+)") (class "Default")
      (node (ref "J1") (pin "D+") (pinfunction "D+_D+") (pintype "bidirectional"))
    )
    (net (code "67") (name "unconnected-(J1-PadD-)") (class "Default")
      (node (ref "J1") (pin "D-") (pinfunction "D-_D-") (pintype "bidirectional"))
    )
    (net (code "68") (name "unconnected-(U1-ADC6-Pad19)") (class "Default")
      (node (ref "U1") (pin "19") (pinfunction "ADC6_19") (pintype "input"))
    )
    (net (code "69") (name "unconnected-(U1-PC0_(ADC0)-Pad23)") (class "Default")
      (node (ref "U1") (pin "23") (pinfunction "PC0_(ADC0)_23") (pintype "bidirectional"))
    )
    (net (code "70") (name "unconnected-(U1-PC2_(ADC2-Pad25)") (class "Default")
      (node (ref "U1") (pin "25") (pinfunction "PC2_(ADC2_25") (pintype "bidirectional"))
    )
    (net (code "71") (name "unconnected-(U2-MUXOUT-Pad30)") (class "Default")
      (node (ref "U2") (pin "30") (pinfunction "MUXOUT_30") (pintype "output"))
    )
    (net (code "72") (name "unconnected-(U2-RFOUTB+-Pad14)") (class "Default")
      (node (ref "U2") (pin "14") (pinfunction "RFOUTB+_14") (pintype "output"))
    )
    (net (code "73") (name "unconnected-(U2-RFOUTB--Pad15)") (class "Default")
      (node (ref "U2") (pin "15") (pinfunction "RFOUTB-_15") (pintype "output"))
    )
    (net (code "74") (name "~{RESET}") (class "Default")
      (node (ref "C4") (pin "2") (pinfunction "2_2") (pintype "passive"))
      (node (ref "ISP") (pin "5") (pinfunction "RESET_5") (pintype "passive"))
      (node (ref "R17") (pin "1") (pinfunction "1_1") (pintype "passive"))
      (node (ref "U1") (pin "29") (pinfunction "PC6_(RESET)_29") (pintype "bidirectional"))
    )
  )
)
